# THERMO_RTD_SENSOR_2CH.net
KiCad netlist of a schematic drawn in Altium Designer
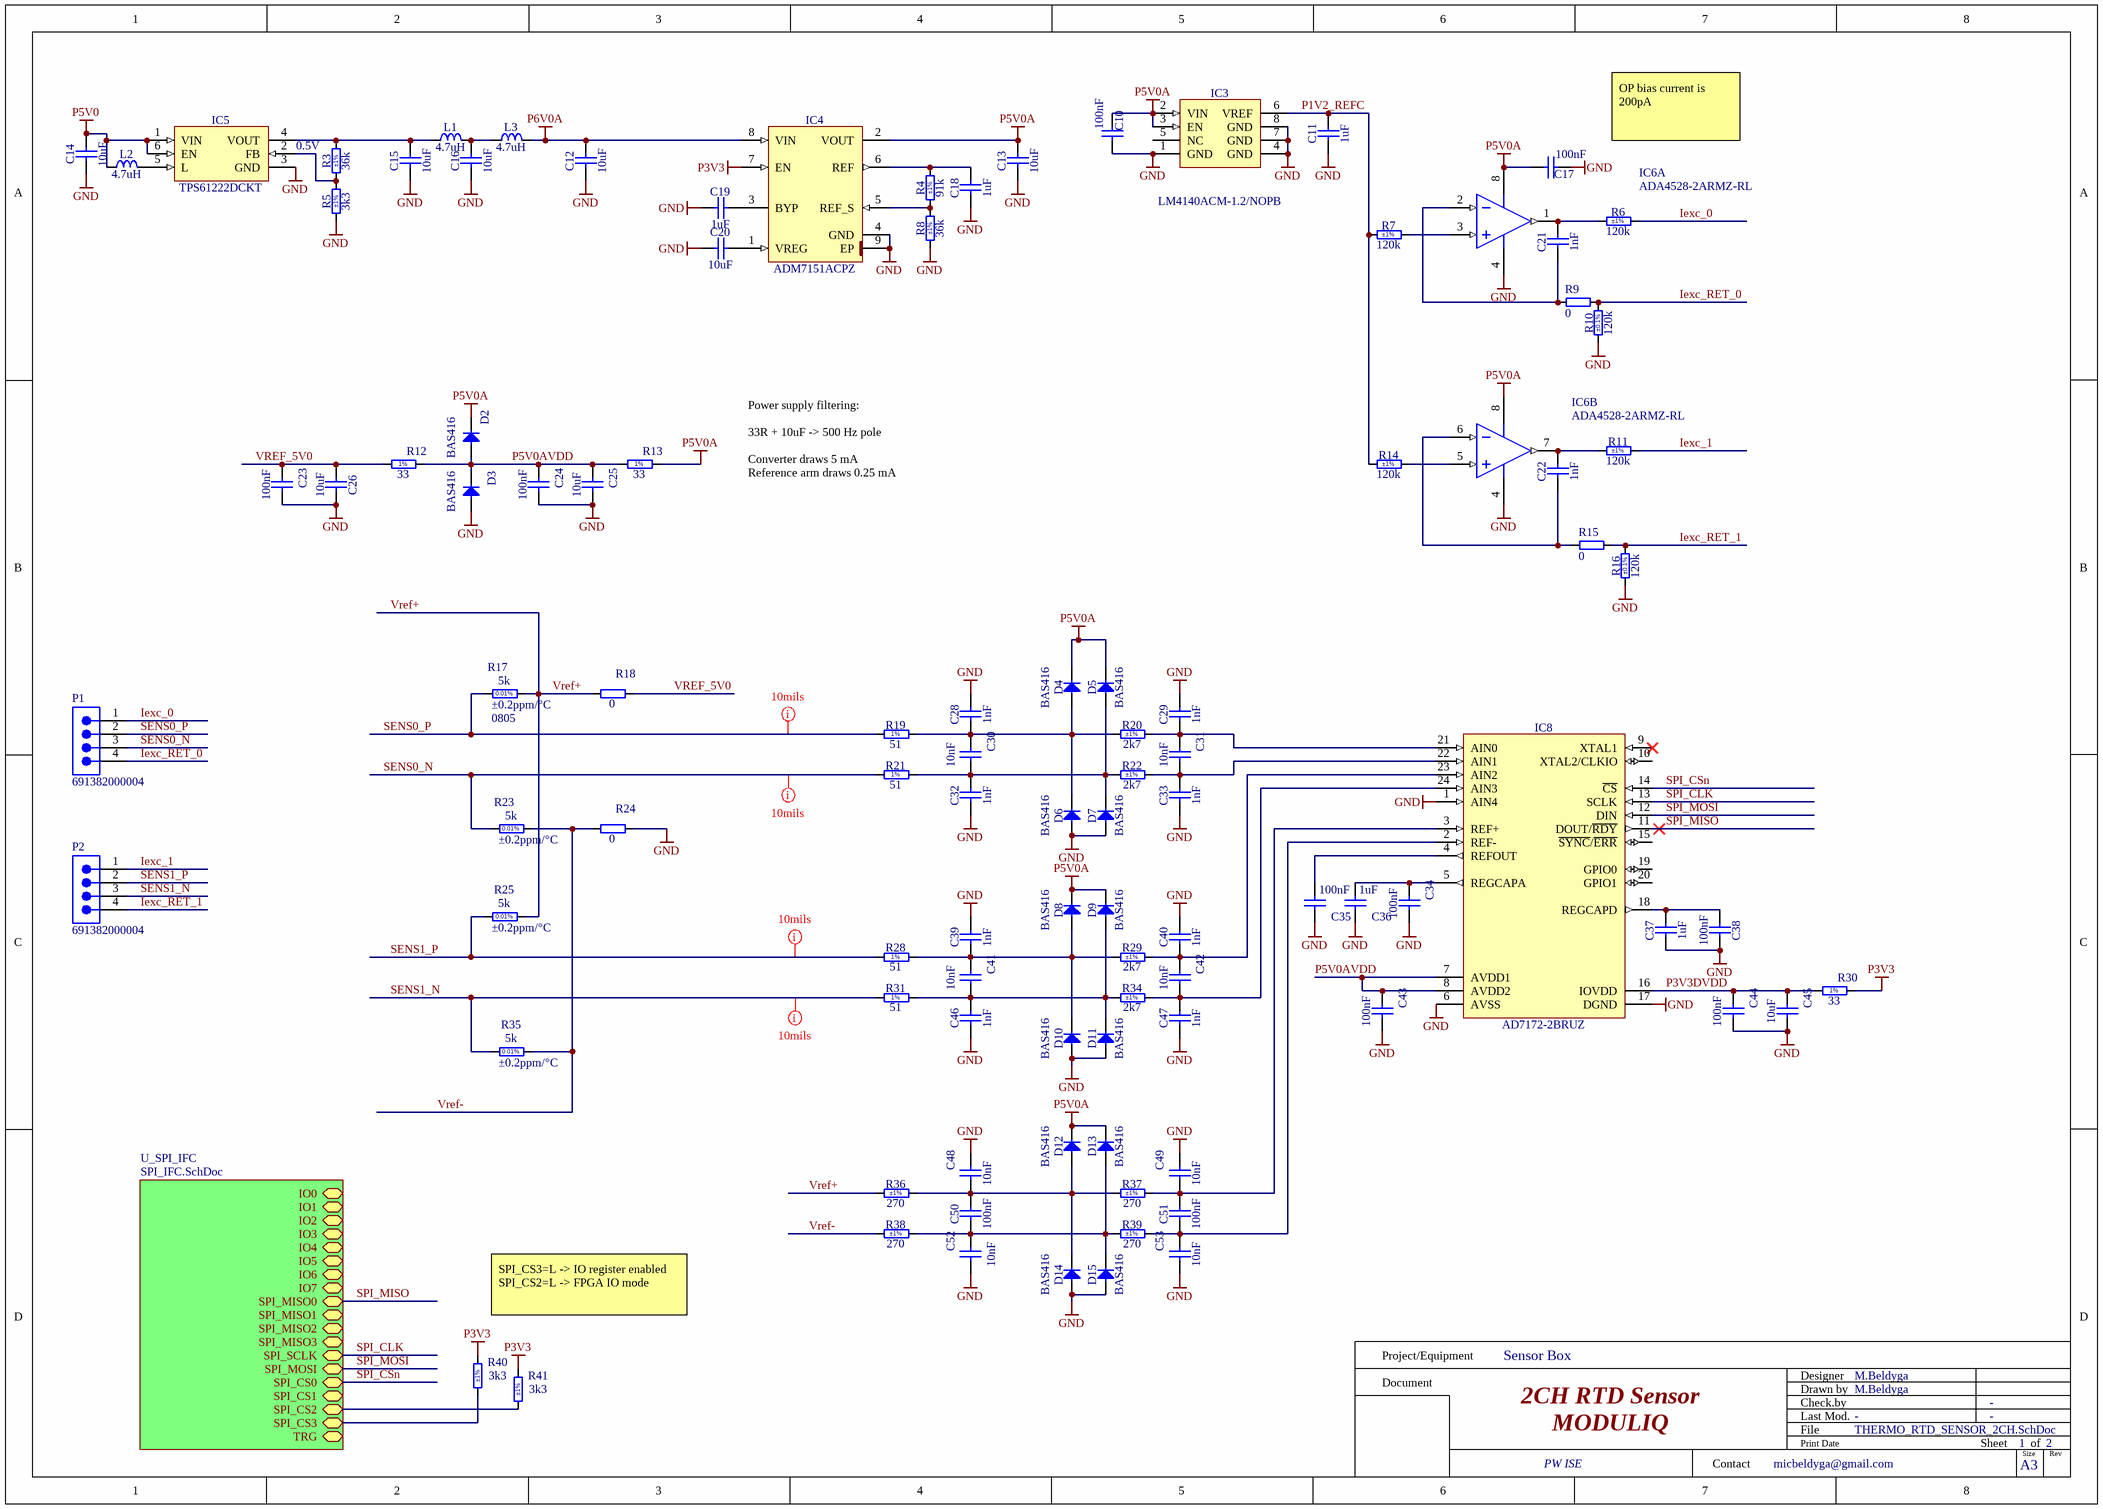
[diagram p0: THERMO_RTD_SENSOR_2CH.SchDoc]

(export (version "E")
  (design (tool "Eeschema 10.0.6"))
  (components
    (comp (ref "C10")
      (value "100nF")
      (footprint "CAPC1005X55N")
      (description "Non-polarised capacitor")
      (fields (field (name "PART NUMBER") "CC0402_100NF_16V_10%_X5R") (field (name "VOLTAGE") "16V"))
      (libsource (lib "Capacitors") (part "Capacitor - non polarized"))
    )
    (comp (ref "C11")
      (value "1uF")
      (footprint "CAPC1608X87N")
      (description "Non-polarised capacitor")
      (fields (field (name "PART NUMBER") "CC0603_1UF_25V_10%_X7R") (field (name "VOLTAGE") "25V"))
      (libsource (lib "Capacitors") (part "Capacitor - non polarized"))
    )
    (comp (ref "C12")
      (value "10uF")
      (footprint "CAPC1608X80N")
      (description "Non-polarised capacitor")
      (fields (field (name "PART NUMBER") "CC0603_10UF_10V_10%_X5R") (field (name "VOLTAGE") "10V"))
      (libsource (lib "Capacitors") (part "Capacitor - non polarized"))
    )
    (comp (ref "C13")
      (value "10uF")
      (footprint "CAPC1608X80N")
      (description "Non-polarised capacitor")
      (fields (field (name "PART NUMBER") "CC0603_10UF_10V_10%_X5R") (field (name "VOLTAGE") "10V"))
      (libsource (lib "Capacitors") (part "Capacitor - non polarized"))
    )
    (comp (ref "C14")
      (value "10uF")
      (footprint "CAPC1608X80N")
      (description "Non-polarised capacitor")
      (fields (field (name "PART NUMBER") "CC0603_10UF_10V_10%_X5R") (field (name "VOLTAGE") "10V"))
      (libsource (lib "Capacitors") (part "Capacitor - non polarized"))
    )
    (comp (ref "C15")
      (value "10uF")
      (footprint "CAPC1608X80N")
      (description "Non-polarised capacitor")
      (fields (field (name "PART NUMBER") "CC0603_10UF_10V_10%_X5R") (field (name "VOLTAGE") "10V"))
      (libsource (lib "Capacitors") (part "Capacitor - non polarized"))
    )
    (comp (ref "C16")
      (value "10uF")
      (footprint "CAPC1608X80N")
      (description "Non-polarised capacitor")
      (fields (field (name "PART NUMBER") "CC0603_10UF_10V_10%_X5R") (field (name "VOLTAGE") "10V"))
      (libsource (lib "Capacitors") (part "Capacitor - non polarized"))
    )
    (comp (ref "C17")
      (value "100nF")
      (footprint "CAPC1005X55N")
      (description "Non-polarised capacitor")
      (fields (field (name "PART NUMBER") "CC0402_100NF_16V_10%_X5R") (field (name "VOLTAGE") "16V"))
      (libsource (lib "Capacitors") (part "Capacitor - non polarized"))
    )
    (comp (ref "C18")
      (value "1uF")
      (footprint "CAPC1005X55N")
      (description "Non-polarised capacitor")
      (fields (field (name "PART NUMBER") "CC0402_1UF_16V_10%_X5R") (field (name "VOLTAGE") "16V"))
      (libsource (lib "Capacitors") (part "Capacitor - non polarized"))
    )
    (comp (ref "C19")
      (value "1uF")
      (footprint "CAPC1005X55N")
      (description "Non-polarised capacitor")
      (fields (field (name "PART NUMBER") "CC0402_1UF_16V_10%_X5R") (field (name "VOLTAGE") "16V"))
      (libsource (lib "Capacitors") (part "Capacitor - non polarized"))
    )
    (comp (ref "C20")
      (value "10uF")
      (footprint "CAPC1608X80N")
      (description "Non-polarised capacitor")
      (fields (field (name "PART NUMBER") "CC0603_10UF_10V_10%_X5R") (field (name "VOLTAGE") "10V"))
      (libsource (lib "Capacitors") (part "Capacitor - non polarized"))
    )
    (comp (ref "C21")
      (value "1nF")
      (footprint "CAPC1005X55N")
      (description "Non-polarised capacitor")
      (fields (field (name "PART NUMBER") "CC0402_1NF_50V_10%_X7R") (field (name "VOLTAGE") "50V"))
      (libsource (lib "Capacitors") (part "Capacitor - non polarized"))
    )
    (comp (ref "C22")
      (value "1nF")
      (footprint "CAPC1005X55N")
      (description "Non-polarised capacitor")
      (fields (field (name "PART NUMBER") "CC0402_1NF_50V_10%_X7R") (field (name "VOLTAGE") "50V"))
      (libsource (lib "Capacitors") (part "Capacitor - non polarized"))
    )
    (comp (ref "C23")
      (value "100nF")
      (footprint "CAPC1005X55N")
      (description "Non-polarised capacitor")
      (fields (field (name "PART NUMBER") "CC0402_100NF_16V_10%_X5R") (field (name "VOLTAGE") "16V"))
      (libsource (lib "Capacitors") (part "Capacitor - non polarized"))
    )
    (comp (ref "C24")
      (value "100nF")
      (footprint "CAPC1005X55N")
      (description "Non-polarised capacitor")
      (fields (field (name "PART NUMBER") "CC0402_100NF_16V_10%_X5R") (field (name "VOLTAGE") "16V"))
      (libsource (lib "Capacitors") (part "Capacitor - non polarized"))
    )
    (comp (ref "C25")
      (value "10uF")
      (footprint "CAPC2012X135N")
      (description "Non-polarised capacitor")
      (fields (field (name "PART NUMBER") "CC0805_10UF_16V_10%_X5R") (field (name "VOLTAGE") "16V"))
      (libsource (lib "Capacitors") (part "Capacitor - non polarized"))
    )
    (comp (ref "C26")
      (value "10uF")
      (footprint "CAPC2012X135N")
      (description "Non-polarised capacitor")
      (fields (field (name "PART NUMBER") "CC0805_10UF_16V_10%_X5R") (field (name "VOLTAGE") "16V"))
      (libsource (lib "Capacitors") (part "Capacitor - non polarized"))
    )
    (comp (ref "C28")
      (value "1nF")
      (footprint "CAPC1608X90N")
      (description "Non-polarised capacitor")
      (fields (field (name "PART NUMBER") "CC0603_1NF_50V_5%_NP0") (field (name "VOLTAGE") "50V"))
      (libsource (lib "Capacitors") (part "Capacitor - non polarized"))
    )
    (comp (ref "C29")
      (value "1nF")
      (footprint "CAPC1608X90N")
      (description "Non-polarised capacitor")
      (fields (field (name "PART NUMBER") "CC0603_1NF_50V_5%_NP0") (field (name "VOLTAGE") "50V"))
      (libsource (lib "Capacitors") (part "Capacitor - non polarized"))
    )
    (comp (ref "C30")
      (value "10nF")
      (footprint "CAPC1608X87N")
      (description "Non-polarised capacitor")
      (fields (field (name "PART NUMBER") "CC0603_10NF_50V_5%_C0G") (field (name "VOLTAGE") "50V"))
      (libsource (lib "Capacitors") (part "Capacitor - non polarized"))
    )
    (comp (ref "C31")
      (value "10nF")
      (footprint "CAPC1608X87N")
      (description "Non-polarised capacitor")
      (fields (field (name "PART NUMBER") "CC0603_10NF_50V_5%_C0G") (field (name "VOLTAGE") "50V"))
      (libsource (lib "Capacitors") (part "Capacitor - non polarized"))
    )
    (comp (ref "C32")
      (value "1nF")
      (footprint "CAPC1608X90N")
      (description "Non-polarised capacitor")
      (fields (field (name "PART NUMBER") "CC0603_1NF_50V_5%_NP0") (field (name "VOLTAGE") "50V"))
      (libsource (lib "Capacitors") (part "Capacitor - non polarized"))
    )
    (comp (ref "C33")
      (value "1nF")
      (footprint "CAPC1608X90N")
      (description "Non-polarised capacitor")
      (fields (field (name "PART NUMBER") "CC0603_1NF_50V_5%_NP0") (field (name "VOLTAGE") "50V"))
      (libsource (lib "Capacitors") (part "Capacitor - non polarized"))
    )
    (comp (ref "C34")
      (value "100nF")
      (footprint "CAPC1005X55N")
      (description "Non-polarised capacitor")
      (fields (field (name "PART NUMBER") "CC0402_100NF_16V_10%_X5R") (field (name "VOLTAGE") "16V"))
      (libsource (lib "Capacitors") (part "Capacitor - non polarized"))
    )
    (comp (ref "C35")
      (value "100nF")
      (footprint "CAPC1005X55N")
      (description "Non-polarised capacitor")
      (fields (field (name "PART NUMBER") "CC0402_100NF_16V_10%_X5R") (field (name "VOLTAGE") "16V"))
      (libsource (lib "Capacitors") (part "Capacitor - non polarized"))
    )
    (comp (ref "C36")
      (value "1uF")
      (footprint "CAPC1608X87N")
      (description "Non-polarised capacitor")
      (fields (field (name "PART NUMBER") "CC0603_1UF_25V_10%_X7R") (field (name "VOLTAGE") "25V"))
      (libsource (lib "Capacitors") (part "Capacitor - non polarized"))
    )
    (comp (ref "C37")
      (value "1uF")
      (footprint "CAPC1608X87N")
      (description "Non-polarised capacitor")
      (fields (field (name "PART NUMBER") "CC0603_1UF_25V_10%_X7R") (field (name "VOLTAGE") "25V"))
      (libsource (lib "Capacitors") (part "Capacitor - non polarized"))
    )
    (comp (ref "C38")
      (value "100nF")
      (footprint "CAPC1005X55N")
      (description "Non-polarised capacitor")
      (fields (field (name "PART NUMBER") "CC0402_100NF_16V_10%_X5R") (field (name "VOLTAGE") "16V"))
      (libsource (lib "Capacitors") (part "Capacitor - non polarized"))
    )
    (comp (ref "C39")
      (value "1nF")
      (footprint "CAPC1608X90N")
      (description "Non-polarised capacitor")
      (fields (field (name "PART NUMBER") "CC0603_1NF_50V_5%_NP0") (field (name "VOLTAGE") "50V"))
      (libsource (lib "Capacitors") (part "Capacitor - non polarized"))
    )
    (comp (ref "C40")
      (value "1nF")
      (footprint "CAPC1608X90N")
      (description "Non-polarised capacitor")
      (fields (field (name "PART NUMBER") "CC0603_1NF_50V_5%_NP0") (field (name "VOLTAGE") "50V"))
      (libsource (lib "Capacitors") (part "Capacitor - non polarized"))
    )
    (comp (ref "C41")
      (value "10nF")
      (footprint "CAPC1608X87N")
      (description "Non-polarised capacitor")
      (fields (field (name "PART NUMBER") "CC0603_10NF_50V_5%_C0G") (field (name "VOLTAGE") "50V"))
      (libsource (lib "Capacitors") (part "Capacitor - non polarized"))
    )
    (comp (ref "C42")
      (value "10nF")
      (footprint "CAPC1608X87N")
      (description "Non-polarised capacitor")
      (fields (field (name "PART NUMBER") "CC0603_10NF_50V_5%_C0G") (field (name "VOLTAGE") "50V"))
      (libsource (lib "Capacitors") (part "Capacitor - non polarized"))
    )
    (comp (ref "C43")
      (value "100nF")
      (footprint "CAPC1005X55N")
      (description "Non-polarised capacitor")
      (fields (field (name "PART NUMBER") "CC0402_100NF_16V_10%_X5R") (field (name "VOLTAGE") "16V"))
      (libsource (lib "Capacitors") (part "Capacitor - non polarized"))
    )
    (comp (ref "C44")
      (value "100nF")
      (footprint "CAPC1005X55N")
      (description "Non-polarised capacitor")
      (fields (field (name "PART NUMBER") "CC0402_100NF_16V_10%_X5R") (field (name "VOLTAGE") "16V"))
      (libsource (lib "Capacitors") (part "Capacitor - non polarized"))
    )
    (comp (ref "C45")
      (value "10uF")
      (footprint "CAPC2012X135N")
      (description "Non-polarised capacitor")
      (fields (field (name "PART NUMBER") "CC0805_10UF_16V_10%_X5R") (field (name "VOLTAGE") "16V"))
      (libsource (lib "Capacitors") (part "Capacitor - non polarized"))
    )
    (comp (ref "C46")
      (value "1nF")
      (footprint "CAPC1608X90N")
      (description "Non-polarised capacitor")
      (fields (field (name "PART NUMBER") "CC0603_1NF_50V_5%_NP0") (field (name "VOLTAGE") "50V"))
      (libsource (lib "Capacitors") (part "Capacitor - non polarized"))
    )
    (comp (ref "C47")
      (value "1nF")
      (footprint "CAPC1608X90N")
      (description "Non-polarised capacitor")
      (fields (field (name "PART NUMBER") "CC0603_1NF_50V_5%_NP0") (field (name "VOLTAGE") "50V"))
      (libsource (lib "Capacitors") (part "Capacitor - non polarized"))
    )
    (comp (ref "C48")
      (value "10nF")
      (footprint "CAPC1608X87N")
      (description "Non-polarised capacitor")
      (fields (field (name "PART NUMBER") "CC0603_10NF_50V_5%_C0G") (field (name "VOLTAGE") "50V"))
      (libsource (lib "Capacitors") (part "Capacitor - non polarized"))
    )
    (comp (ref "C49")
      (value "10nF")
      (footprint "CAPC1608X87N")
      (description "Non-polarised capacitor")
      (fields (field (name "PART NUMBER") "CC0603_10NF_50V_5%_C0G") (field (name "VOLTAGE") "50V"))
      (libsource (lib "Capacitors") (part "Capacitor - non polarized"))
    )
    (comp (ref "C50")
      (value "100nF")
      (footprint "CAPC1608X87N")
      (description "Non-polarised capacitor")
      (fields (field (name "PART NUMBER") "CC0603_100NF_50V_10%_X5R") (field (name "VOLTAGE") "50V"))
      (libsource (lib "Capacitors") (part "Capacitor - non polarized"))
    )
    (comp (ref "C51")
      (value "100nF")
      (footprint "CAPC1608X87N")
      (description "Non-polarised capacitor")
      (fields (field (name "PART NUMBER") "CC0603_100NF_50V_10%_X5R") (field (name "VOLTAGE") "50V"))
      (libsource (lib "Capacitors") (part "Capacitor - non polarized"))
    )
    (comp (ref "C52")
      (value "10nF")
      (footprint "CAPC1608X87N")
      (description "Non-polarised capacitor")
      (fields (field (name "PART NUMBER") "CC0603_10NF_50V_5%_C0G") (field (name "VOLTAGE") "50V"))
      (libsource (lib "Capacitors") (part "Capacitor - non polarized"))
    )
    (comp (ref "C53")
      (value "10nF")
      (footprint "CAPC1608X87N")
      (description "Non-polarised capacitor")
      (fields (field (name "PART NUMBER") "CC0603_10NF_50V_5%_C0G") (field (name "VOLTAGE") "50V"))
      (libsource (lib "Capacitors") (part "Capacitor - non polarized"))
    )
    (comp (ref "D2")
      (value "BAS416")
      (footprint "SOD2512X110N")
      (description "Diode")
      (fields (field (name "VOLTAGE") "75V") (field (name "POWER") "200mA"))
      (libsource (lib "ICs And Semiconductors") (part "Diode"))
    )
    (comp (ref "D3")
      (value "BAS416")
      (footprint "SOD2512X110N")
      (description "Diode")
      (fields (field (name "VOLTAGE") "75V") (field (name "POWER") "200mA"))
      (libsource (lib "ICs And Semiconductors") (part "Diode"))
    )
    (comp (ref "D4")
      (value "BAS416")
      (footprint "SOD2512X110N")
      (description "Diode")
      (fields (field (name "VOLTAGE") "75V") (field (name "POWER") "200mA"))
      (libsource (lib "ICs And Semiconductors") (part "Diode"))
    )
    (comp (ref "D5")
      (value "BAS416")
      (footprint "SOD2512X110N")
      (description "Diode")
      (fields (field (name "VOLTAGE") "75V") (field (name "POWER") "200mA"))
      (libsource (lib "ICs And Semiconductors") (part "Diode"))
    )
    (comp (ref "D6")
      (value "BAS416")
      (footprint "SOD2512X110N")
      (description "Diode")
      (fields (field (name "VOLTAGE") "75V") (field (name "POWER") "200mA"))
      (libsource (lib "ICs And Semiconductors") (part "Diode"))
    )
    (comp (ref "D7")
      (value "BAS416")
      (footprint "SOD2512X110N")
      (description "Diode")
      (fields (field (name "VOLTAGE") "75V") (field (name "POWER") "200mA"))
      (libsource (lib "ICs And Semiconductors") (part "Diode"))
    )
    (comp (ref "D8")
      (value "BAS416")
      (footprint "SOD2512X110N")
      (description "Diode")
      (fields (field (name "VOLTAGE") "75V") (field (name "POWER") "200mA"))
      (libsource (lib "ICs And Semiconductors") (part "Diode"))
    )
    (comp (ref "D9")
      (value "BAS416")
      (footprint "SOD2512X110N")
      (description "Diode")
      (fields (field (name "VOLTAGE") "75V") (field (name "POWER") "200mA"))
      (libsource (lib "ICs And Semiconductors") (part "Diode"))
    )
    (comp (ref "D10")
      (value "BAS416")
      (footprint "SOD2512X110N")
      (description "Diode")
      (fields (field (name "VOLTAGE") "75V") (field (name "POWER") "200mA"))
      (libsource (lib "ICs And Semiconductors") (part "Diode"))
    )
    (comp (ref "D11")
      (value "BAS416")
      (footprint "SOD2512X110N")
      (description "Diode")
      (fields (field (name "VOLTAGE") "75V") (field (name "POWER") "200mA"))
      (libsource (lib "ICs And Semiconductors") (part "Diode"))
    )
    (comp (ref "D12")
      (value "BAS416")
      (footprint "SOD2512X110N")
      (description "Diode")
      (fields (field (name "VOLTAGE") "75V") (field (name "POWER") "200mA"))
      (libsource (lib "ICs And Semiconductors") (part "Diode"))
    )
    (comp (ref "D13")
      (value "BAS416")
      (footprint "SOD2512X110N")
      (description "Diode")
      (fields (field (name "VOLTAGE") "75V") (field (name "POWER") "200mA"))
      (libsource (lib "ICs And Semiconductors") (part "Diode"))
    )
    (comp (ref "D14")
      (value "BAS416")
      (footprint "SOD2512X110N")
      (description "Diode")
      (fields (field (name "VOLTAGE") "75V") (field (name "POWER") "200mA"))
      (libsource (lib "ICs And Semiconductors") (part "Diode"))
    )
    (comp (ref "D15")
      (value "BAS416")
      (footprint "SOD2512X110N")
      (description "Diode")
      (fields (field (name "VOLTAGE") "75V") (field (name "POWER") "200mA"))
      (libsource (lib "ICs And Semiconductors") (part "Diode"))
    )
    (comp (ref "IC3")
      (value "LM4140ACM-1.2/NOPB")
      (footprint "SOIC127P600X175-8N")
      (description "High Precision Low Noise Low Dropout Voltage Reference")
      (fields (field (name "MANUFACTURER") "TEXAS INSTRUMENTS"))
      (libsource (lib "ICs And Semiconductors") (part "LM4140"))
    )
    (comp (ref "IC4")
      (value "ADM7151ACPZ")
      (footprint "SON50P300X300X80-9N-R170X244")
      (description "800 mA Ultralow Noise, High PSRR, RF Linear Regulator")
      (fields
        (field (name "MANUFACTURER") "ANALOG DEVICES")
        (field (name "MANUFACTURER PART NUMBER") "ADM7151ACP")
      )
      (libsource (lib "ICs And Semiconductors") (part "ADM7151"))
    )
    (comp (ref "IC5")
      (value "TPS61222DCKT")
      (footprint "SOT65P210X110-6N")
      (description "Low Input Voltage, 0.7V Boost Converter With 5.5uA Quiescent Current")
      (fields
        (field (name "MANUFACTURER") "TEXAS INSTRUMENTS")
        (field (name "MANUFACTURER PART NUMBER") "TPS61222DCK")
      )
      (libsource (lib "ICs And Semiconductors") (part "TPS61222"))
    )
    (comp (ref "IC6")
      (value "ADA4528-2ARMZ-RL")
      (footprint "ADI-RM-8_N")
      (fields (field (name "GENERIC PART NUMBER") "ADA4528-2") (field (name "MANUFACTURER") "Analog Devices"))
      (libsource (lib "Altium Content Vault") (part "ADI-ADA4000-2-X-8"))
    )
    (comp (ref "IC8")
      (value "AD7172-2BRUZ")
      (footprint "SOP65P640X120-24N")
      (description "32-Bit, 10 kSPS, Sigma-Delta ADC with 100 µs Settling and True Rail-to-Rail Buffers")
      (fields (field (name "MANUFACTURER") "ANALOG DEVICES"))
      (libsource (lib "LIBRARY_SCH") (part "ADC_AD7172-2"))
    )
    (comp (ref "L1")
      (value "4.7uH")
      (footprint "INDC2520X120N")
      (description "Inductor")
      (fields (field (name "PART NUMBER") "IND1008_4.7UH_20%_MURATA_DFE252012P") (field (name "POWER") "2A"))
      (libsource (lib "Inductors & Transformers") (part "Inductor"))
    )
    (comp (ref "L2")
      (value "4.7uH")
      (footprint "INDC2520X120N")
      (description "Inductor")
      (fields (field (name "PART NUMBER") "IND1008_4.7UH_20%_MURATA_DFE252012P") (field (name "POWER") "2A"))
      (libsource (lib "Inductors & Transformers") (part "Inductor"))
    )
    (comp (ref "L3")
      (value "4.7uH")
      (footprint "INDC2520X120N")
      (description "Inductor")
      (fields (field (name "PART NUMBER") "IND1008_4.7UH_20%_MURATA_DFE252012P") (field (name "POWER") "2A"))
      (libsource (lib "Inductors & Transformers") (part "Inductor"))
    )
    (comp (ref "P1")
      (value "691382000004")
      (footprint "691382000004")
      (description "WR-TBL Series 382 Vertical PCB Header, THT, pitch 2.5mm, 4p")
      (fields (field (name "MANUFACTURER") "Wurth Elektronik"))
      (libsource (lib "WE - Electromechanical Components") (part "TBL - 1R - 04P - Male"))
    )
    (comp (ref "P2")
      (value "691382000004")
      (footprint "691382000004")
      (description "WR-TBL Series 382 Vertical PCB Header, THT, pitch 2.5mm, 4p")
      (fields (field (name "MANUFACTURER") "Wurth Elektronik"))
      (libsource (lib "WE - Electromechanical Components") (part "TBL - 1R - 04P - Male"))
    )
    (comp (ref "R3")
      (value "36k")
      (footprint "RESC1005X40N")
      (description "Resistor - 1%")
      (fields
        (field (name "TOLERANCE") "±1%")
        (field (name "PART NUMBER") "R0402_36K_1%_0.0625W_100PPM")
        (field (name "POWER") "0.0625W")
      )
      (libsource (lib "Resistors") (part "Resistor - 1%"))
    )
    (comp (ref "R4")
      (value "91k")
      (footprint "RESC1005X40N")
      (description "Resistor - 1%")
      (fields
        (field (name "TOLERANCE") "±1%")
        (field (name "PART NUMBER") "R0402_91K_1%_0.0625W_100PPM")
        (field (name "POWER") "0.0625W")
      )
      (libsource (lib "Resistors") (part "Resistor - 1%"))
    )
    (comp (ref "R5")
      (value "3k3")
      (footprint "RESC1005X40N")
      (description "Resistor - 1%")
      (fields
        (field (name "TOLERANCE") "±1%")
        (field (name "PART NUMBER") "R0402_3K3_1%_0.0625W_100PPM")
        (field (name "POWER") "0.0625W")
      )
      (libsource (lib "Resistors") (part "Resistor - 1%"))
    )
    (comp (ref "R6")
      (value "120k")
      (footprint "RESC1005X40N")
      (description "Resistor - 1%")
      (fields
        (field (name "TOLERANCE") "±1%")
        (field (name "PART NUMBER") "R0402_120K_1%_0.0625W_100PPM")
        (field (name "POWER") "0.0625W")
      )
      (libsource (lib "Resistors") (part "Resistor - 1%"))
    )
    (comp (ref "R7")
      (value "120k")
      (footprint "RESC1005X40N")
      (description "Resistor - 1%")
      (fields
        (field (name "TOLERANCE") "±1%")
        (field (name "PART NUMBER") "R0402_120K_1%_0.0625W_100PPM")
        (field (name "POWER") "0.0625W")
      )
      (libsource (lib "Resistors") (part "Resistor - 1%"))
    )
    (comp (ref "R8")
      (value "36k")
      (footprint "RESC1005X40N")
      (description "Resistor - 1%")
      (fields
        (field (name "TOLERANCE") "±1%")
        (field (name "PART NUMBER") "R0402_36K_1%_0.0625W_100PPM")
        (field (name "POWER") "0.0625W")
      )
      (libsource (lib "Resistors") (part "Resistor - 1%"))
    )
    (comp (ref "R9")
      (value "0")
      (footprint "RESC1005X40N")
      (description "Resistor")
      (fields (field (name "PART NUMBER") "R0402_0R_JUMPER") (field (name "MANUFACTURER") "GENERIC"))
      (libsource (lib "Resistors") (part "Resistor"))
    )
    (comp (ref "R10")
      (value "120k")
      (footprint "RESC2012X60N")
      (description "Resistor - 0.1%")
      (fields
        (field (name "TOLERANCE") "±0.1%")
        (field (name "PART NUMBER") "R0805_120K_0.1%_0.125W_25PPM")
        (field (name "POWER") "0.125W")
      )
      (libsource (lib "Resistors") (part "Resistor - 0.1%"))
    )
    (comp (ref "R11")
      (value "120k")
      (footprint "RESC1005X40N")
      (description "Resistor - 1%")
      (fields
        (field (name "TOLERANCE") "±1%")
        (field (name "PART NUMBER") "R0402_120K_1%_0.0625W_100PPM")
        (field (name "POWER") "0.0625W")
      )
      (libsource (lib "Resistors") (part "Resistor - 1%"))
    )
    (comp (ref "R12")
      (value "33")
      (footprint "RESC1005X40N")
      (description "Resistor - 1%")
      (fields (field (name "PART NUMBER") "R0402_33R_1%_0.0625W_100PPM") (field (name "POWER") "0.0625W"))
      (libsource (lib "Resistors") (part "Resistor - 1%"))
    )
    (comp (ref "R13")
      (value "33")
      (footprint "RESC1005X40N")
      (description "Resistor - 1%")
      (fields (field (name "PART NUMBER") "R0402_33R_1%_0.0625W_100PPM") (field (name "POWER") "0.0625W"))
      (libsource (lib "Resistors") (part "Resistor - 1%"))
    )
    (comp (ref "R14")
      (value "120k")
      (footprint "RESC1005X40N")
      (description "Resistor - 1%")
      (fields
        (field (name "TOLERANCE") "±1%")
        (field (name "PART NUMBER") "R0402_120K_1%_0.0625W_100PPM")
        (field (name "POWER") "0.0625W")
      )
      (libsource (lib "Resistors") (part "Resistor - 1%"))
    )
    (comp (ref "R15")
      (value "0")
      (footprint "RESC1005X40N")
      (description "Resistor")
      (fields (field (name "PART NUMBER") "R0402_0R_JUMPER") (field (name "MANUFACTURER") "GENERIC"))
      (libsource (lib "Resistors") (part "Resistor"))
    )
    (comp (ref "R16")
      (value "120k")
      (footprint "RESC2012X60N")
      (description "Resistor - 0.1%")
      (fields
        (field (name "TOLERANCE") "±0.1%")
        (field (name "PART NUMBER") "R0805_120K_0.1%_0.125W_25PPM")
        (field (name "POWER") "0.125W")
      )
      (libsource (lib "Resistors") (part "Resistor - 0.1%"))
    )
    (comp (ref "R17")
      (value "5k")
      (footprint "RESC2013X64N")
      (description "Resistor - 0.01%")
      (fields
        (field (name "PART NUMBER") "R0805_5K_0.01%_0.2W_0.2PPM_VISHAY_VSMP")
        (field (name "POWER") "0.2W")
        (field (name "TC") "±0.2ppm/°C")
        (field (name "CASE") "0805")
      )
      (libsource (lib "Resistors") (part "Resistor - 0.01%"))
    )
    (comp (ref "R18")
      (value "0")
      (footprint "RESC1608X55N")
      (description "Resistor")
      (fields (field (name "PART NUMBER") "R0603_0R_JUMPER") (field (name "MANUFACTURER") "GENERIC"))
      (libsource (lib "Resistors") (part "Resistor"))
    )
    (comp (ref "R19")
      (value "51")
      (footprint "RESC1005X40N")
      (description "Resistor - 1%")
      (fields (field (name "PART NUMBER") "R0402_51R_1%_0.0625W_100PPM") (field (name "POWER") "0.0625W"))
      (libsource (lib "Resistors") (part "Resistor - 1%"))
    )
    (comp (ref "R20")
      (value "2k7")
      (footprint "RESC1005X40N")
      (description "Resistor - 1%")
      (fields
        (field (name "TOLERANCE") "±1%")
        (field (name "PART NUMBER") "R0402_2K7_1%_0.0625W_100PPM")
        (field (name "POWER") "0.0625W")
      )
      (libsource (lib "Resistors") (part "Resistor - 1%"))
    )
    (comp (ref "R21")
      (value "51")
      (footprint "RESC1005X40N")
      (description "Resistor - 1%")
      (fields (field (name "PART NUMBER") "R0402_51R_1%_0.0625W_100PPM") (field (name "POWER") "0.0625W"))
      (libsource (lib "Resistors") (part "Resistor - 1%"))
    )
    (comp (ref "R22")
      (value "2k7")
      (footprint "RESC1005X40N")
      (description "Resistor - 1%")
      (fields
        (field (name "TOLERANCE") "±1%")
        (field (name "PART NUMBER") "R0402_2K7_1%_0.0625W_100PPM")
        (field (name "POWER") "0.0625W")
      )
      (libsource (lib "Resistors") (part "Resistor - 1%"))
    )
    (comp (ref "R23")
      (value "5k")
      (footprint "RESC2013X64N")
      (description "Resistor - 0.01%")
      (fields
        (field (name "PART NUMBER") "R0805_5K_0.01%_0.2W_0.2PPM_VISHAY_VSMP")
        (field (name "POWER") "0.2W")
        (field (name "TC") "±0.2ppm/°C")
      )
      (libsource (lib "Resistors") (part "Resistor - 0.01%"))
    )
    (comp (ref "R24")
      (value "0")
      (footprint "RESC1608X55N")
      (description "Resistor")
      (fields (field (name "PART NUMBER") "R0603_0R_JUMPER") (field (name "MANUFACTURER") "GENERIC"))
      (libsource (lib "Resistors") (part "Resistor"))
    )
    (comp (ref "R25")
      (value "5k")
      (footprint "RESC2013X64N")
      (description "Resistor - 0.01%")
      (fields
        (field (name "PART NUMBER") "R0805_5K_0.01%_0.2W_0.2PPM_VISHAY_VSMP")
        (field (name "POWER") "0.2W")
        (field (name "TC") "±0.2ppm/°C")
      )
      (libsource (lib "Resistors") (part "Resistor - 0.01%"))
    )
    (comp (ref "R28")
      (value "51")
      (footprint "RESC1005X40N")
      (description "Resistor - 1%")
      (fields (field (name "PART NUMBER") "R0402_51R_1%_0.0625W_100PPM") (field (name "POWER") "0.0625W"))
      (libsource (lib "Resistors") (part "Resistor - 1%"))
    )
    (comp (ref "R29")
      (value "2k7")
      (footprint "RESC1005X40N")
      (description "Resistor - 1%")
      (fields
        (field (name "TOLERANCE") "±1%")
        (field (name "PART NUMBER") "R0402_2K7_1%_0.0625W_100PPM")
        (field (name "POWER") "0.0625W")
      )
      (libsource (lib "Resistors") (part "Resistor - 1%"))
    )
    (comp (ref "R30")
      (value "33")
      (footprint "RESC1005X40N")
      (description "Resistor - 1%")
      (fields (field (name "PART NUMBER") "R0402_33R_1%_0.0625W_100PPM") (field (name "POWER") "0.0625W"))
      (libsource (lib "Resistors") (part "Resistor - 1%"))
    )
    (comp (ref "R31")
      (value "51")
      (footprint "RESC1005X40N")
      (description "Resistor - 1%")
      (fields (field (name "PART NUMBER") "R0402_51R_1%_0.0625W_100PPM") (field (name "POWER") "0.0625W"))
      (libsource (lib "Resistors") (part "Resistor - 1%"))
    )
    (comp (ref "R34")
      (value "2k7")
      (footprint "RESC1005X40N")
      (description "Resistor - 1%")
      (fields
        (field (name "TOLERANCE") "±1%")
        (field (name "PART NUMBER") "R0402_2K7_1%_0.0625W_100PPM")
        (field (name "POWER") "0.0625W")
      )
      (libsource (lib "Resistors") (part "Resistor - 1%"))
    )
    (comp (ref "R35")
      (value "5k")
      (footprint "RESC2013X64N")
      (description "Resistor - 0.01%")
      (fields
        (field (name "PART NUMBER") "R0805_5K_0.01%_0.2W_0.2PPM_VISHAY_VSMP")
        (field (name "POWER") "0.2W")
        (field (name "TC") "±0.2ppm/°C")
      )
      (libsource (lib "Resistors") (part "Resistor - 0.01%"))
    )
    (comp (ref "R36")
      (value "270")
      (footprint "RESC1005X40N")
      (description "Resistor - 1%")
      (fields
        (field (name "TOLERANCE") "±1%")
        (field (name "PART NUMBER") "R0402_270R_1%_0.0625W_100PPM")
        (field (name "POWER") "0.0625W")
      )
      (libsource (lib "Resistors") (part "Resistor - 1%"))
    )
    (comp (ref "R37")
      (value "270")
      (footprint "RESC1005X40N")
      (description "Resistor - 1%")
      (fields
        (field (name "TOLERANCE") "±1%")
        (field (name "PART NUMBER") "R0402_270R_1%_0.0625W_100PPM")
        (field (name "POWER") "0.0625W")
      )
      (libsource (lib "Resistors") (part "Resistor - 1%"))
    )
    (comp (ref "R38")
      (value "270")
      (footprint "RESC1005X40N")
      (description "Resistor - 1%")
      (fields
        (field (name "TOLERANCE") "±1%")
        (field (name "PART NUMBER") "R0402_270R_1%_0.0625W_100PPM")
        (field (name "POWER") "0.0625W")
      )
      (libsource (lib "Resistors") (part "Resistor - 1%"))
    )
    (comp (ref "R39")
      (value "270")
      (footprint "RESC1005X40N")
      (description "Resistor - 1%")
      (fields
        (field (name "TOLERANCE") "±1%")
        (field (name "PART NUMBER") "R0402_270R_1%_0.0625W_100PPM")
        (field (name "POWER") "0.0625W")
      )
      (libsource (lib "Resistors") (part "Resistor - 1%"))
    )
    (comp (ref "R40")
      (value "3k3")
      (footprint "RESC1005X40N")
      (description "Resistor - 1%")
      (fields
        (field (name "TOLERANCE") "±1%")
        (field (name "PART NUMBER") "R0402_3K3_1%_0.0625W_100PPM")
        (field (name "POWER") "0.0625W")
      )
      (libsource (lib "Resistors") (part "Resistor - 1%"))
    )
    (comp (ref "R41")
      (value "3k3")
      (footprint "RESC1005X40N")
      (description "Resistor - 1%")
      (fields
        (field (name "TOLERANCE") "±1%")
        (field (name "PART NUMBER") "R0402_3K3_1%_0.0625W_100PPM")
        (field (name "POWER") "0.0625W")
      )
      (libsource (lib "Resistors") (part "Resistor - 1%"))
    )
  )
  (nets
    (net (code "9") (name "/Iexc_0") (class "Default")
      (node (ref "P1") (pin "1") (pinfunction "1_1") (pintype "passive"))
      (node (ref "R6") (pin "2") (pinfunction "2_2") (pintype "passive"))
    )
    (net (code "10") (name "/Iexc_1") (class "Default")
      (node (ref "P2") (pin "1") (pinfunction "1_1") (pintype "passive"))
      (node (ref "R11") (pin "2") (pinfunction "2_2") (pintype "passive"))
    )
    (net (code "11") (name "/Iexc_RET_0") (class "Default")
      (node (ref "P1") (pin "4") (pinfunction "4_4") (pintype "passive"))
      (node (ref "R10") (pin "2") (pinfunction "2_2") (pintype "passive"))
      (node (ref "R9") (pin "2") (pinfunction "2_2") (pintype "passive"))
    )
    (net (code "12") (name "/Iexc_RET_1") (class "Default")
      (node (ref "P2") (pin "4") (pinfunction "4_4") (pintype "passive"))
      (node (ref "R15") (pin "2") (pinfunction "2_2") (pintype "passive"))
      (node (ref "R16") (pin "2") (pinfunction "2_2") (pintype "passive"))
    )
    (net (code "13") (name "/P1V2_REFC") (class "Default")
      (node (ref "C11") (pin "2") (pinfunction "2_2") (pintype "passive"))
      (node (ref "IC3") (pin "6") (pinfunction "VREF_6") (pintype "power_in"))
      (node (ref "R14") (pin "1") (pinfunction "1_1") (pintype "passive"))
      (node (ref "R7") (pin "1") (pinfunction "1_1") (pintype "passive"))
    )
    (net (code "14") (name "/P3V3DVDD") (class "Default")
      (node (ref "C44") (pin "1") (pinfunction "1_1") (pintype "passive"))
      (node (ref "C45") (pin "1") (pinfunction "1_1") (pintype "passive"))
      (node (ref "IC8") (pin "16") (pinfunction "IOVDD_16") (pintype "power_in"))
      (node (ref "R30") (pin "1") (pinfunction "1_1") (pintype "passive"))
    )
    (net (code "15") (name "/P5V0AVDD") (class "Default")
      (node (ref "C24") (pin "1") (pinfunction "1_1") (pintype "passive"))
      (node (ref "C25") (pin "1") (pinfunction "1_1") (pintype "passive"))
      (node (ref "C43") (pin "1") (pinfunction "1_1") (pintype "passive"))
      (node (ref "D2") (pin "2") (pinfunction "A_2") (pintype "passive"))
      (node (ref "D3") (pin "1") (pinfunction "C_1") (pintype "passive"))
      (node (ref "IC8") (pin "7") (pinfunction "AVDD1_7") (pintype "power_in"))
      (node (ref "IC8") (pin "8") (pinfunction "AVDD2_8") (pintype "power_in"))
      (node (ref "R12") (pin "2") (pinfunction "2_2") (pintype "passive"))
      (node (ref "R13") (pin "1") (pinfunction "1_1") (pintype "passive"))
    )
    (net (code "16") (name "/SENS0_N") (class "Default")
      (node (ref "P1") (pin "3") (pinfunction "3_3") (pintype "passive"))
      (node (ref "R21") (pin "1") (pinfunction "1_1") (pintype "passive"))
      (node (ref "R23") (pin "1") (pinfunction "1_1") (pintype "passive"))
    )
    (net (code "17") (name "/SENS0_P") (class "Default")
      (node (ref "P1") (pin "2") (pinfunction "2_2") (pintype "passive"))
      (node (ref "R17") (pin "1") (pinfunction "1_1") (pintype "passive"))
      (node (ref "R19") (pin "1") (pinfunction "1_1") (pintype "passive"))
    )
    (net (code "18") (name "/SENS1_N") (class "Default")
      (node (ref "P2") (pin "3") (pinfunction "3_3") (pintype "passive"))
      (node (ref "R31") (pin "1") (pinfunction "1_1") (pintype "passive"))
      (node (ref "R35") (pin "1") (pinfunction "1_1") (pintype "passive"))
    )
    (net (code "19") (name "/SENS1_P") (class "Default")
      (node (ref "P2") (pin "2") (pinfunction "2_2") (pintype "passive"))
      (node (ref "R25") (pin "1") (pinfunction "1_1") (pintype "passive"))
      (node (ref "R28") (pin "1") (pinfunction "1_1") (pintype "passive"))
    )
    (net (code "20") (name "/SPI_CLK") (class "Default")
      (node (ref "IC8") (pin "13") (pinfunction "SCLK_13") (pintype "input"))
    )
    (net (code "22") (name "/SPI_CS2") (class "Default")
      (node (ref "R41") (pin "2") (pinfunction "2_2") (pintype "passive"))
    )
    (net (code "23") (name "/SPI_CS3") (class "Default")
      (node (ref "R40") (pin "2") (pinfunction "2_2") (pintype "passive"))
    )
    (net (code "24") (name "/SPI_CSn") (class "Default")
      (node (ref "IC8") (pin "14") (pinfunction "~{CS}_14") (pintype "input"))
    )
    (net (code "25") (name "/SPI_MISO") (class "Default")
      (node (ref "IC8") (pin "11") (pinfunction "DOUT/~{RDY}_11") (pintype "output"))
    )
    (net (code "29") (name "/SPI_MOSI") (class "Default")
      (node (ref "IC8") (pin "12") (pinfunction "DIN_12") (pintype "input"))
    )
    (net (code "31") (name "/VREF_5V0") (class "Default")
      (node (ref "C23") (pin "1") (pinfunction "1_1") (pintype "passive"))
      (node (ref "C26") (pin "1") (pinfunction "1_1") (pintype "passive"))
      (node (ref "R12") (pin "1") (pinfunction "1_1") (pintype "passive"))
      (node (ref "R18") (pin "2") (pinfunction "2_2") (pintype "passive"))
    )
    (net (code "32") (name "/Vref+") (class "Default")
      (node (ref "R17") (pin "2") (pinfunction "2_2") (pintype "passive"))
      (node (ref "R18") (pin "1") (pinfunction "1_1") (pintype "passive"))
      (node (ref "R25") (pin "2") (pinfunction "2_2") (pintype "passive"))
      (node (ref "R36") (pin "1") (pinfunction "1_1") (pintype "passive"))
    )
    (net (code "33") (name "/Vref-") (class "Default")
      (node (ref "R23") (pin "2") (pinfunction "2_2") (pintype "passive"))
      (node (ref "R24") (pin "1") (pinfunction "1_1") (pintype "passive"))
      (node (ref "R35") (pin "2") (pinfunction "2_2") (pintype "passive"))
      (node (ref "R38") (pin "1") (pinfunction "1_1") (pintype "passive"))
    )
    (net (code "34") (name "GND") (class "Default")
      (node (ref "C10") (pin "2") (pinfunction "2_2") (pintype "passive"))
      (node (ref "C11") (pin "1") (pinfunction "1_1") (pintype "passive"))
      (node (ref "C12") (pin "1") (pinfunction "1_1") (pintype "passive"))
      (node (ref "C13") (pin "1") (pinfunction "1_1") (pintype "passive"))
      (node (ref "C14") (pin "1") (pinfunction "1_1") (pintype "passive"))
      (node (ref "C15") (pin "1") (pinfunction "1_1") (pintype "passive"))
      (node (ref "C16") (pin "1") (pinfunction "1_1") (pintype "passive"))
      (node (ref "C17") (pin "1") (pinfunction "1_1") (pintype "passive"))
      (node (ref "C18") (pin "1") (pinfunction "1_1") (pintype "passive"))
      (node (ref "C19") (pin "1") (pinfunction "1_1") (pintype "passive"))
      (node (ref "C20") (pin "1") (pinfunction "1_1") (pintype "passive"))
      (node (ref "C23") (pin "2") (pinfunction "2_2") (pintype "passive"))
      (node (ref "C24") (pin "2") (pinfunction "2_2") (pintype "passive"))
      (node (ref "C25") (pin "2") (pinfunction "2_2") (pintype "passive"))
      (node (ref "C26") (pin "2") (pinfunction "2_2") (pintype "passive"))
      (node (ref "C28") (pin "2") (pinfunction "2_2") (pintype "passive"))
      (node (ref "C29") (pin "2") (pinfunction "2_2") (pintype "passive"))
      (node (ref "C32") (pin "1") (pinfunction "1_1") (pintype "passive"))
      (node (ref "C33") (pin "1") (pinfunction "1_1") (pintype "passive"))
      (node (ref "C34") (pin "2") (pinfunction "2_2") (pintype "passive"))
      (node (ref "C35") (pin "2") (pinfunction "2_2") (pintype "passive"))
      (node (ref "C36") (pin "1") (pinfunction "1_1") (pintype "passive"))
      (node (ref "C37") (pin "1") (pinfunction "1_1") (pintype "passive"))
      (node (ref "C38") (pin "2") (pinfunction "2_2") (pintype "passive"))
      (node (ref "C39") (pin "2") (pinfunction "2_2") (pintype "passive"))
      (node (ref "C40") (pin "2") (pinfunction "2_2") (pintype "passive"))
      (node (ref "C43") (pin "2") (pinfunction "2_2") (pintype "passive"))
      (node (ref "C44") (pin "2") (pinfunction "2_2") (pintype "passive"))
      (node (ref "C45") (pin "2") (pinfunction "2_2") (pintype "passive"))
      (node (ref "C46") (pin "1") (pinfunction "1_1") (pintype "passive"))
      (node (ref "C47") (pin "1") (pinfunction "1_1") (pintype "passive"))
      (node (ref "C48") (pin "2") (pinfunction "2_2") (pintype "passive"))
      (node (ref "C49") (pin "2") (pinfunction "2_2") (pintype "passive"))
      (node (ref "C52") (pin "1") (pinfunction "1_1") (pintype "passive"))
      (node (ref "C53") (pin "1") (pinfunction "1_1") (pintype "passive"))
      (node (ref "D10") (pin "2") (pinfunction "A_2") (pintype "passive"))
      (node (ref "D11") (pin "2") (pinfunction "A_2") (pintype "passive"))
      (node (ref "D14") (pin "2") (pinfunction "A_2") (pintype "passive"))
      (node (ref "D15") (pin "2") (pinfunction "A_2") (pintype "passive"))
      (node (ref "D3") (pin "2") (pinfunction "A_2") (pintype "passive"))
      (node (ref "D6") (pin "2") (pinfunction "A_2") (pintype "passive"))
      (node (ref "D7") (pin "2") (pinfunction "A_2") (pintype "passive"))
      (node (ref "IC3") (pin "1") (pinfunction "GND_1") (pintype "power_in"))
      (node (ref "IC3") (pin "4") (pinfunction "GND_4") (pintype "power_in"))
      (node (ref "IC3") (pin "7") (pinfunction "GND_7") (pintype "power_in"))
      (node (ref "IC3") (pin "8") (pinfunction "GND_8") (pintype "power_in"))
      (node (ref "IC4") (pin "4") (pinfunction "GND_4") (pintype "power_in"))
      (node (ref "IC4") (pin "9") (pinfunction "EP_9") (pintype "power_in"))
      (node (ref "IC5") (pin "3") (pinfunction "GND_3") (pintype "power_in"))
      (node (ref "IC6") (pin "4") (pinfunction "-V_4") (pintype "power_in"))
      (node (ref "IC8") (pin "1") (pinfunction "AIN4_1") (pintype "input"))
      (node (ref "IC8") (pin "17") (pinfunction "DGND_17") (pintype "power_in"))
      (node (ref "IC8") (pin "6") (pinfunction "AVSS_6") (pintype "power_in"))
      (node (ref "R10") (pin "1") (pinfunction "1_1") (pintype "passive"))
      (node (ref "R16") (pin "1") (pinfunction "1_1") (pintype "passive"))
      (node (ref "R24") (pin "2") (pinfunction "2_2") (pintype "passive"))
      (node (ref "R5") (pin "1") (pinfunction "1_1") (pintype "passive"))
      (node (ref "R8") (pin "1") (pinfunction "1_1") (pintype "passive"))
    )
    (net (code "35") (name "Net-(C16-Pad2)") (class "Default")
      (node (ref "C16") (pin "2") (pinfunction "2_2") (pintype "passive"))
      (node (ref "L1") (pin "2") (pinfunction "2_2") (pintype "passive"))
      (node (ref "L3") (pin "1") (pinfunction "1_1") (pintype "passive"))
    )
    (net (code "36") (name "Net-(D4-A)") (class "Default")
      (node (ref "C28") (pin "1") (pinfunction "1_1") (pintype "passive"))
      (node (ref "C30") (pin "1") (pinfunction "1_1") (pintype "passive"))
      (node (ref "D4") (pin "2") (pinfunction "A_2") (pintype "passive"))
      (node (ref "D6") (pin "1") (pinfunction "C_1") (pintype "passive"))
      (node (ref "R19") (pin "2") (pinfunction "2_2") (pintype "passive"))
      (node (ref "R20") (pin "1") (pinfunction "1_1") (pintype "passive"))
    )
    (net (code "37") (name "Net-(D5-A)") (class "Default")
      (node (ref "C30") (pin "2") (pinfunction "2_2") (pintype "passive"))
      (node (ref "C32") (pin "2") (pinfunction "2_2") (pintype "passive"))
      (node (ref "D5") (pin "2") (pinfunction "A_2") (pintype "passive"))
      (node (ref "D7") (pin "1") (pinfunction "C_1") (pintype "passive"))
      (node (ref "R21") (pin "2") (pinfunction "2_2") (pintype "passive"))
      (node (ref "R22") (pin "1") (pinfunction "1_1") (pintype "passive"))
    )
    (net (code "38") (name "Net-(D10-C)") (class "Default")
      (node (ref "C39") (pin "1") (pinfunction "1_1") (pintype "passive"))
      (node (ref "C41") (pin "1") (pinfunction "1_1") (pintype "passive"))
      (node (ref "D10") (pin "1") (pinfunction "C_1") (pintype "passive"))
      (node (ref "D8") (pin "2") (pinfunction "A_2") (pintype "passive"))
      (node (ref "R28") (pin "2") (pinfunction "2_2") (pintype "passive"))
      (node (ref "R29") (pin "1") (pinfunction "1_1") (pintype "passive"))
    )
    (net (code "39") (name "Net-(D11-C)") (class "Default")
      (node (ref "C41") (pin "2") (pinfunction "2_2") (pintype "passive"))
      (node (ref "C46") (pin "2") (pinfunction "2_2") (pintype "passive"))
      (node (ref "D11") (pin "1") (pinfunction "C_1") (pintype "passive"))
      (node (ref "D9") (pin "2") (pinfunction "A_2") (pintype "passive"))
      (node (ref "R31") (pin "2") (pinfunction "2_2") (pintype "passive"))
      (node (ref "R34") (pin "1") (pinfunction "1_1") (pintype "passive"))
    )
    (net (code "40") (name "Net-(D12-A)") (class "Default")
      (node (ref "C48") (pin "1") (pinfunction "1_1") (pintype "passive"))
      (node (ref "C50") (pin "2") (pinfunction "2_2") (pintype "passive"))
      (node (ref "D12") (pin "2") (pinfunction "A_2") (pintype "passive"))
      (node (ref "D14") (pin "1") (pinfunction "C_1") (pintype "passive"))
      (node (ref "R36") (pin "2") (pinfunction "2_2") (pintype "passive"))
      (node (ref "R37") (pin "1") (pinfunction "1_1") (pintype "passive"))
    )
    (net (code "41") (name "Net-(D13-A)") (class "Default")
      (node (ref "C50") (pin "1") (pinfunction "1_1") (pintype "passive"))
      (node (ref "C52") (pin "2") (pinfunction "2_2") (pintype "passive"))
      (node (ref "D13") (pin "2") (pinfunction "A_2") (pintype "passive"))
      (node (ref "D15") (pin "1") (pinfunction "C_1") (pintype "passive"))
      (node (ref "R38") (pin "2") (pinfunction "2_2") (pintype "passive"))
      (node (ref "R39") (pin "1") (pinfunction "1_1") (pintype "passive"))
    )
    (net (code "42") (name "Net-(IC4-BYP)") (class "Default")
      (node (ref "C19") (pin "2") (pinfunction "2_2") (pintype "passive"))
      (node (ref "IC4") (pin "3") (pinfunction "BYP_3") (pintype "passive"))
    )
    (net (code "43") (name "Net-(IC4-REF)") (class "Default")
      (node (ref "C18") (pin "2") (pinfunction "2_2") (pintype "passive"))
      (node (ref "IC4") (pin "6") (pinfunction "REF_6") (pintype "output"))
      (node (ref "R4") (pin "2") (pinfunction "2_2") (pintype "passive"))
    )
    (net (code "44") (name "Net-(IC4-REF_S)") (class "Default")
      (node (ref "IC4") (pin "5") (pinfunction "REF_S_5") (pintype "input"))
      (node (ref "R4") (pin "1") (pinfunction "1_1") (pintype "passive"))
      (node (ref "R8") (pin "2") (pinfunction "2_2") (pintype "passive"))
    )
    (net (code "45") (name "Net-(IC4-VREG)") (class "Default")
      (node (ref "C20") (pin "2") (pinfunction "2_2") (pintype "passive"))
      (node (ref "IC4") (pin "1") (pinfunction "VREG_1") (pintype "input"))
    )
    (net (code "46") (name "Net-(IC5-FB)") (class "Default")
      (node (ref "IC5") (pin "2") (pinfunction "FB_2") (pintype "input"))
      (node (ref "R3") (pin "1") (pinfunction "1_1") (pintype "passive"))
      (node (ref "R5") (pin "2") (pinfunction "2_2") (pintype "passive"))
    )
    (net (code "47") (name "Net-(IC5-L)") (class "Default")
      (node (ref "IC5") (pin "5") (pinfunction "L_5") (pintype "input"))
      (node (ref "L2") (pin "2") (pinfunction "2_2") (pintype "passive"))
    )
    (net (code "48") (name "Net-(IC5-VOUT)") (class "Default")
      (node (ref "C15") (pin "2") (pinfunction "2_2") (pintype "passive"))
      (node (ref "IC5") (pin "4") (pinfunction "VOUT_4") (pintype "power_in"))
      (node (ref "L1") (pin "1") (pinfunction "1_1") (pintype "passive"))
      (node (ref "R3") (pin "2") (pinfunction "2_2") (pintype "passive"))
    )
    (net (code "49") (name "Net-(IC6A-+IN_A)") (class "Default")
      (node (ref "IC6") (pin "3") (pinfunction "+IN_A_3") (pintype "input"))
      (node (ref "R7") (pin "2") (pinfunction "2_2") (pintype "passive"))
    )
    (net (code "50") (name "Net-(IC6A--IN_A)") (class "Default")
      (node (ref "C21") (pin "1") (pinfunction "1_1") (pintype "passive"))
      (node (ref "IC6") (pin "2") (pinfunction "-IN_A_2") (pintype "input"))
      (node (ref "R9") (pin "1") (pinfunction "1_1") (pintype "passive"))
    )
    (net (code "51") (name "Net-(IC6A-OUT_A)") (class "Default")
      (node (ref "C21") (pin "2") (pinfunction "2_2") (pintype "passive"))
      (node (ref "IC6") (pin "1") (pinfunction "OUT_A_1") (pintype "output"))
      (node (ref "R6") (pin "1") (pinfunction "1_1") (pintype "passive"))
    )
    (net (code "52") (name "Net-(IC6B-+IN_B)") (class "Default")
      (node (ref "IC6") (pin "5") (pinfunction "+IN_B_5") (pintype "input"))
      (node (ref "R14") (pin "2") (pinfunction "2_2") (pintype "passive"))
    )
    (net (code "53") (name "Net-(IC6B--IN_B)") (class "Default")
      (node (ref "C22") (pin "1") (pinfunction "1_1") (pintype "passive"))
      (node (ref "IC6") (pin "6") (pinfunction "-IN_B_6") (pintype "input"))
      (node (ref "R15") (pin "1") (pinfunction "1_1") (pintype "passive"))
    )
    (net (code "54") (name "Net-(IC6B-OUT_B)") (class "Default")
      (node (ref "C22") (pin "2") (pinfunction "2_2") (pintype "passive"))
      (node (ref "IC6") (pin "7") (pinfunction "OUT_B_7") (pintype "output"))
      (node (ref "R11") (pin "1") (pinfunction "1_1") (pintype "passive"))
    )
    (net (code "55") (name "Net-(IC8-AIN0)") (class "Default")
      (node (ref "C29") (pin "1") (pinfunction "1_1") (pintype "passive"))
      (node (ref "C31") (pin "1") (pinfunction "1_1") (pintype "passive"))
      (node (ref "IC8") (pin "21") (pinfunction "AIN0_21") (pintype "input"))
      (node (ref "R20") (pin "2") (pinfunction "2_2") (pintype "passive"))
    )
    (net (code "56") (name "Net-(IC8-AIN1)") (class "Default")
      (node (ref "C31") (pin "2") (pinfunction "2_2") (pintype "passive"))
      (node (ref "C33") (pin "2") (pinfunction "2_2") (pintype "passive"))
      (node (ref "IC8") (pin "22") (pinfunction "AIN1_22") (pintype "input"))
      (node (ref "R22") (pin "2") (pinfunction "2_2") (pintype "passive"))
    )
    (net (code "57") (name "Net-(IC8-AIN2)") (class "Default")
      (node (ref "C40") (pin "1") (pinfunction "1_1") (pintype "passive"))
      (node (ref "C42") (pin "1") (pinfunction "1_1") (pintype "passive"))
      (node (ref "IC8") (pin "23") (pinfunction "AIN2_23") (pintype "input"))
      (node (ref "R29") (pin "2") (pinfunction "2_2") (pintype "passive"))
    )
    (net (code "58") (name "Net-(IC8-AIN3)") (class "Default")
      (node (ref "C42") (pin "2") (pinfunction "2_2") (pintype "passive"))
      (node (ref "C47") (pin "2") (pinfunction "2_2") (pintype "passive"))
      (node (ref "IC8") (pin "24") (pinfunction "AIN3_24") (pintype "input"))
      (node (ref "R34") (pin "2") (pinfunction "2_2") (pintype "passive"))
    )
    (net (code "59") (name "Net-(IC8-REF+)") (class "Default")
      (node (ref "C49") (pin "1") (pinfunction "1_1") (pintype "passive"))
      (node (ref "C51") (pin "2") (pinfunction "2_2") (pintype "passive"))
      (node (ref "IC8") (pin "3") (pinfunction "REF+_3") (pintype "input"))
      (node (ref "R37") (pin "2") (pinfunction "2_2") (pintype "passive"))
    )
    (net (code "60") (name "Net-(IC8-REF-)") (class "Default")
      (node (ref "C51") (pin "1") (pinfunction "1_1") (pintype "passive"))
      (node (ref "C53") (pin "2") (pinfunction "2_2") (pintype "passive"))
      (node (ref "IC8") (pin "2") (pinfunction "REF-_2") (pintype "input"))
      (node (ref "R39") (pin "2") (pinfunction "2_2") (pintype "passive"))
    )
    (net (code "61") (name "Net-(IC8-REFOUT)") (class "Default")
      (node (ref "C35") (pin "1") (pinfunction "1_1") (pintype "passive"))
      (node (ref "IC8") (pin "4") (pinfunction "REFOUT_4") (pintype "output"))
    )
    (net (code "62") (name "Net-(IC8-REGCAPA)") (class "Default")
      (node (ref "C34") (pin "1") (pinfunction "1_1") (pintype "passive"))
      (node (ref "C36") (pin "2") (pinfunction "2_2") (pintype "passive"))
      (node (ref "IC8") (pin "5") (pinfunction "REGCAPA_5") (pintype "output"))
    )
    (net (code "63") (name "Net-(IC8-REGCAPD)") (class "Default")
      (node (ref "C37") (pin "2") (pinfunction "2_2") (pintype "passive"))
      (node (ref "C38") (pin "1") (pinfunction "1_1") (pintype "passive"))
      (node (ref "IC8") (pin "18") (pinfunction "REGCAPD_18") (pintype "output"))
    )
    (net (code "64") (name "P3V3") (class "Default")
      (node (ref "IC4") (pin "7") (pinfunction "EN_7") (pintype "input"))
      (node (ref "R30") (pin "2") (pinfunction "2_2") (pintype "passive"))
      (node (ref "R40") (pin "1") (pinfunction "1_1") (pintype "passive"))
      (node (ref "R41") (pin "1") (pinfunction "1_1") (pintype "passive"))
    )
    (net (code "65") (name "P5V0") (class "Default")
      (node (ref "C14") (pin "2") (pinfunction "2_2") (pintype "passive"))
      (node (ref "IC5") (pin "1") (pinfunction "VIN_1") (pintype "input"))
      (node (ref "IC5") (pin "6") (pinfunction "EN_6") (pintype "input"))
      (node (ref "L2") (pin "1") (pinfunction "1_1") (pintype "passive"))
    )
    (net (code "66") (name "P5V0A") (class "Default")
      (node (ref "C10") (pin "1") (pinfunction "1_1") (pintype "passive"))
      (node (ref "C13") (pin "2") (pinfunction "2_2") (pintype "passive"))
      (node (ref "C17") (pin "2") (pinfunction "2_2") (pintype "passive"))
      (node (ref "D12") (pin "1") (pinfunction "C_1") (pintype "passive"))
      (node (ref "D13") (pin "1") (pinfunction "C_1") (pintype "passive"))
      (node (ref "D2") (pin "1") (pinfunction "C_1") (pintype "passive"))
      (node (ref "D4") (pin "1") (pinfunction "C_1") (pintype "passive"))
      (node (ref "D5") (pin "1") (pinfunction "C_1") (pintype "passive"))
      (node (ref "D8") (pin "1") (pinfunction "C_1") (pintype "passive"))
      (node (ref "D9") (pin "1") (pinfunction "C_1") (pintype "passive"))
      (node (ref "IC3") (pin "2") (pinfunction "VIN_2") (pintype "input"))
      (node (ref "IC3") (pin "3") (pinfunction "EN_3") (pintype "input"))
      (node (ref "IC4") (pin "2") (pinfunction "VOUT_2") (pintype "power_in"))
      (node (ref "IC6") (pin "8") (pinfunction "+V_8") (pintype "power_in"))
      (node (ref "R13") (pin "2") (pinfunction "2_2") (pintype "passive"))
    )
    (net (code "67") (name "P6V0A") (class "Default")
      (node (ref "C12") (pin "2") (pinfunction "2_2") (pintype "passive"))
      (node (ref "IC4") (pin "8") (pinfunction "VIN_8") (pintype "input"))
      (node (ref "L3") (pin "2") (pinfunction "2_2") (pintype "passive"))
    )
    (net (code "68") (name "unconnected-(IC3-NC-Pad5)") (class "Default")
      (node (ref "IC3") (pin "5") (pinfunction "NC_5") (pintype "passive"))
    )
    (net (code "69") (name "unconnected-(IC8-GPIO0-Pad19)") (class "Default")
      (node (ref "IC8") (pin "19") (pinfunction "GPIO0_19") (pintype "bidirectional"))
    )
    (net (code "70") (name "unconnected-(IC8-GPIO1-Pad20)") (class "Default")
      (node (ref "IC8") (pin "20") (pinfunction "GPIO1_20") (pintype "bidirectional"))
    )
    (net (code "71") (name "unconnected-(IC8-XTAL1-Pad9)") (class "Default")
      (node (ref "IC8") (pin "9") (pinfunction "XTAL1_9") (pintype "input+no_connect"))
    )
    (net (code "72") (name "unconnected-(IC8-XTAL2{slash}CLKIO-Pad10)") (class "Default")
      (node (ref "IC8") (pin "10") (pinfunction "XTAL2/CLKIO_10") (pintype "bidirectional"))
    )
    (net (code "73") (name "unconnected-(IC8-~{SYNC}{slash}~{ERR}-Pad15)") (class "Default")
      (node (ref "IC8") (pin "15") (pinfunction "~{SYNC}/~{ERR}_15") (pintype "bidirectional"))
    )
  )
)
